# EMMC_SDcard.net
KiCad netlist of a schematic drawn in Altium Designer
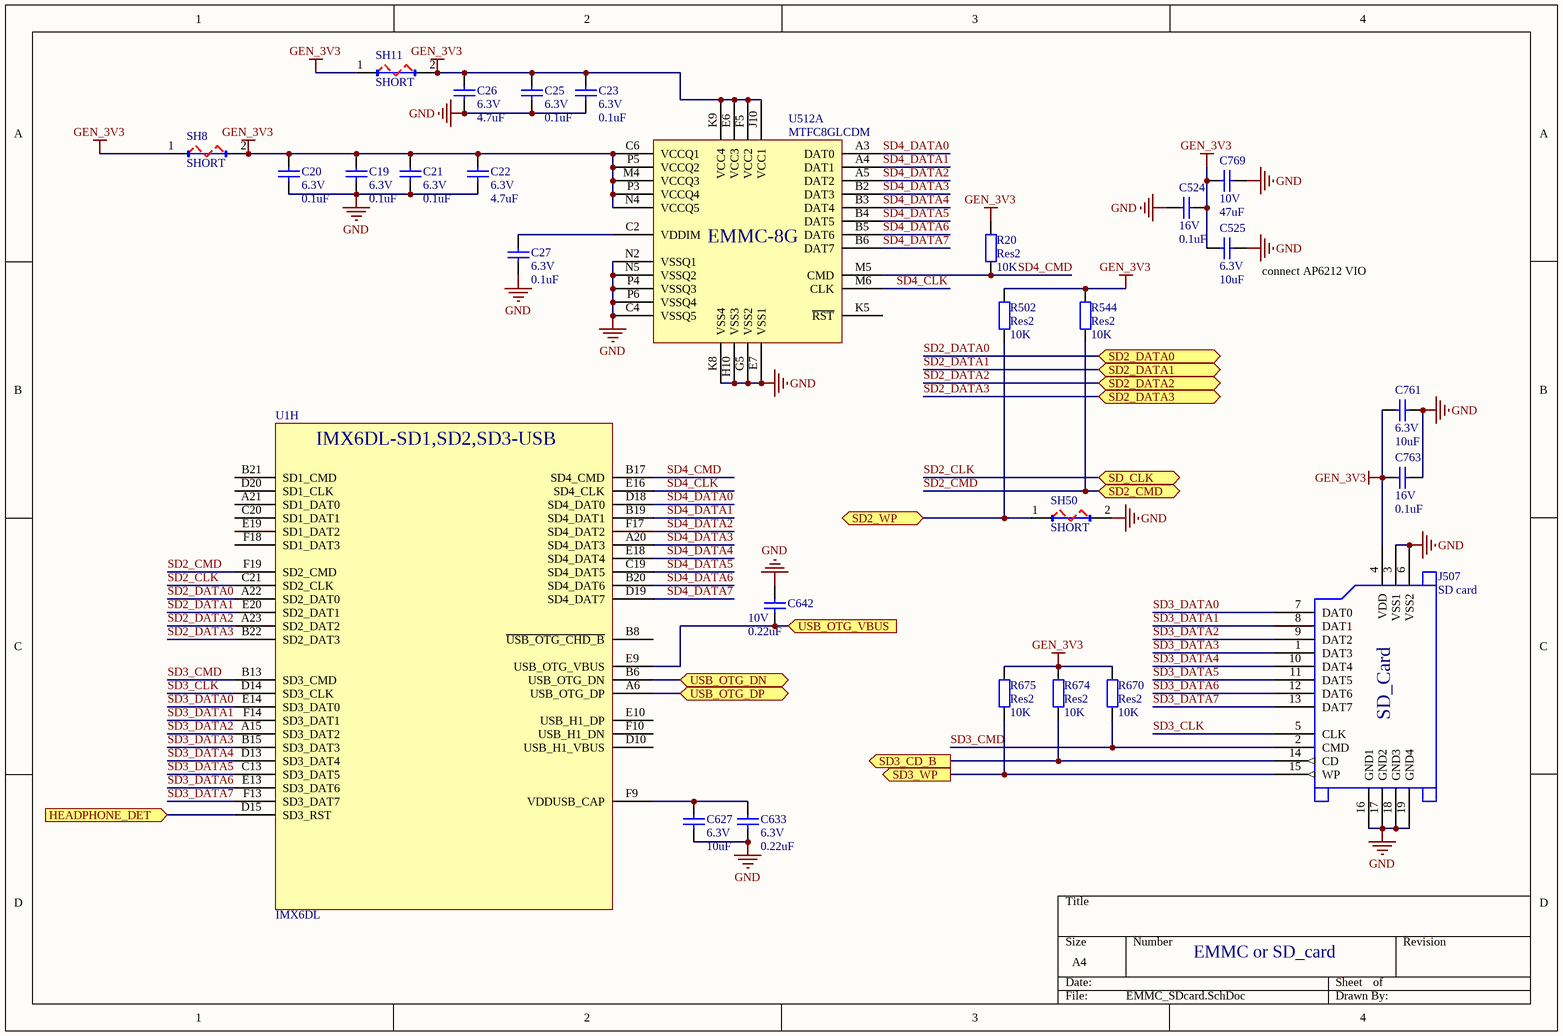
[diagram p0: EMMC_SDcard.SchDoc]

(export (version "E")
  (design (tool "Eeschema 10.0.6"))
  (components
    (comp (ref "C19")
      (value "6.3V")
      (footprint "0201")
      (description "Capacitor")
      (fields (field (name "ALTIUM_VALUE") "0.1uF") (field (name "PUBLISHER") "Altium Limited"))
      (libsource (lib "Miscellaneous Devices") (part "Cap"))
    )
    (comp (ref "C20")
      (value "6.3V")
      (footprint "0201")
      (description "Capacitor")
      (fields (field (name "ALTIUM_VALUE") "0.1uF") (field (name "PUBLISHER") "Altium Limited"))
      (libsource (lib "Miscellaneous Devices") (part "Cap"))
    )
    (comp (ref "C21")
      (value "6.3V")
      (footprint "0201")
      (description "Capacitor")
      (fields (field (name "ALTIUM_VALUE") "0.1uF") (field (name "PUBLISHER") "Altium Limited"))
      (libsource (lib "Miscellaneous Devices") (part "Cap"))
    )
    (comp (ref "C22")
      (value "6.3V")
      (footprint "0603")
      (description "Capacitor")
      (fields (field (name "ALTIUM_VALUE") "4.7uF") (field (name "PUBLISHER") "Altium Limited"))
      (libsource (lib "Miscellaneous Devices") (part "Cap"))
    )
    (comp (ref "C23")
      (value "6.3V")
      (footprint "0201")
      (description "Capacitor")
      (fields (field (name "ALTIUM_VALUE") "0.1uF") (field (name "PUBLISHER") "Altium Limited"))
      (libsource (lib "Miscellaneous Devices") (part "Cap"))
    )
    (comp (ref "C25")
      (value "6.3V")
      (footprint "0201")
      (description "Capacitor")
      (fields (field (name "ALTIUM_VALUE") "0.1uF") (field (name "PUBLISHER") "Altium Limited"))
      (libsource (lib "Miscellaneous Devices") (part "Cap"))
    )
    (comp (ref "C26")
      (value "6.3V")
      (footprint "0603")
      (description "Capacitor")
      (fields (field (name "ALTIUM_VALUE") "4.7uF") (field (name "PUBLISHER") "Altium Limited"))
      (libsource (lib "Miscellaneous Devices") (part "Cap"))
    )
    (comp (ref "C27")
      (value "6.3V")
      (footprint "0201")
      (description "Capacitor")
      (fields (field (name "ALTIUM_VALUE") "0.1uF") (field (name "PUBLISHER") "Altium Limited"))
      (libsource (lib "Miscellaneous Devices") (part "Cap"))
    )
    (comp (ref "C524")
      (value "16V")
      (footprint "0402")
      (description "Capacitor")
      (fields (field (name "ALTIUM_VALUE") "0.1uF") (field (name "PUBLISHER") "Altium Limited"))
      (libsource (lib "Miscellaneous Devices") (part "Cap"))
    )
    (comp (ref "C525")
      (value "6.3V")
      (footprint "0603")
      (description "Capacitor")
      (fields (field (name "ALTIUM_VALUE") "10uF") (field (name "PUBLISHER") "Altium Limited"))
      (libsource (lib "Miscellaneous Devices") (part "Cap"))
    )
    (comp (ref "C627")
      (value "6.3V")
      (footprint "0603")
      (description "Capacitor")
      (fields (field (name "ALTIUM_VALUE") "10uF") (field (name "PUBLISHER") "Altium Limited"))
      (libsource (lib "Miscellaneous Devices") (part "Cap"))
    )
    (comp (ref "C633")
      (value "6.3V")
      (footprint "0201")
      (description "Capacitor")
      (fields (field (name "ALTIUM_VALUE") "0.22uF") (field (name "PUBLISHER") "Altium Limited"))
      (libsource (lib "Miscellaneous Devices") (part "Cap"))
    )
    (comp (ref "C642")
      (value "10V")
      (footprint "0201")
      (description "Capacitor")
      (fields (field (name "ALTIUM_VALUE") "0.22uF") (field (name "PUBLISHER") "Altium Limited"))
      (libsource (lib "Miscellaneous Devices") (part "Cap"))
    )
    (comp (ref "C761")
      (value "6.3V")
      (footprint "0603")
      (description "Capacitor")
      (fields (field (name "ALTIUM_VALUE") "10uF") (field (name "PUBLISHER") "Altium Limited"))
      (libsource (lib "Miscellaneous Devices") (part "Cap"))
    )
    (comp (ref "C763")
      (value "16V")
      (footprint "0402")
      (description "Capacitor")
      (fields (field (name "ALTIUM_VALUE") "0.1uF") (field (name "PUBLISHER") "Altium Limited"))
      (libsource (lib "Miscellaneous Devices") (part "Cap"))
    )
    (comp (ref "C769")
      (value "10V")
      (footprint "nonpolarity_cap_1206")
      (description "Capacitor")
      (fields (field (name "ALTIUM_VALUE") "47uF") (field (name "PUBLISHER") "Altium Limited"))
      (libsource (lib "Miscellaneous Devices") (part "Cap"))
    )
    (comp (ref "J507") (value "SD card") (footprint "SD_card") (libsource (lib "IMX6DL") (part "SD card")))
    (comp (ref "R20")
      (value "Res2")
      (footprint "0402")
      (description "Resistor")
      (fields (field (name "ALTIUM_VALUE") "10K") (field (name "PUBLISHER") "Altium Limited"))
      (libsource (lib "Miscellaneous Devices") (part "Res2"))
    )
    (comp (ref "R502")
      (value "Res2")
      (footprint "0402")
      (description "Resistor")
      (fields (field (name "ALTIUM_VALUE") "10K") (field (name "PUBLISHER") "Altium Limited"))
      (libsource (lib "Miscellaneous Devices") (part "Res2"))
    )
    (comp (ref "R544")
      (value "Res2")
      (footprint "0402")
      (description "Resistor")
      (fields (field (name "ALTIUM_VALUE") "10K") (field (name "PUBLISHER") "Altium Limited"))
      (libsource (lib "Miscellaneous Devices") (part "Res2"))
    )
    (comp (ref "R670")
      (value "Res2")
      (footprint "0402")
      (description "Resistor")
      (fields (field (name "ALTIUM_VALUE") "10K") (field (name "PUBLISHER") "Altium Limited"))
      (libsource (lib "Miscellaneous Devices") (part "Res2"))
    )
    (comp (ref "R674")
      (value "Res2")
      (footprint "0402")
      (description "Resistor")
      (fields (field (name "ALTIUM_VALUE") "10K") (field (name "PUBLISHER") "Altium Limited"))
      (libsource (lib "Miscellaneous Devices") (part "Res2"))
    )
    (comp (ref "R675")
      (value "Res2")
      (footprint "0402")
      (description "Resistor")
      (fields (field (name "ALTIUM_VALUE") "10K") (field (name "PUBLISHER") "Altium Limited"))
      (libsource (lib "Miscellaneous Devices") (part "Res2"))
    )
    (comp (ref "SH8") (value "SHORT") (footprint "SHORT_SH") (libsource (lib "IMX6DL") (part "SOLDER SHORT")))
    (comp (ref "SH11")
      (value "SHORT")
      (footprint "SHORT_SH")
      (libsource (lib "IMX6DL") (part "SOLDER SHORT"))
    )
    (comp (ref "SH50")
      (value "SHORT")
      (footprint "SHORT_SH")
      (libsource (lib "IMX6DL") (part "SOLDER SHORT"))
    )
    (comp (ref "U1")
      (value "IMX6DL")
      (footprint "IMX6DL-BGA624x25")
      (libsource (lib "IMX6DL") (part "IMX6DL"))
    )
    (comp (ref "U512A")
      (value "MTFC8GLCDM")
      (footprint "SDIN8DE2-4G-EMMC-BGA153")
      (libsource (lib "IMX6DL") (part "MTFC8GLCDM-emmc"))
    )
  )
  (nets
    (net (code "1") (name "/HEADPHONE_DET") (class "Default")
      (node (ref "U1") (pin "D15") (pinfunction "SD3_RST_D15") (pintype "passive"))
    )
    (net (code "2") (name "/SD2_CLK") (class "Default")
      (node (ref "U1") (pin "C21") (pinfunction "SD2_CLK_C21") (pintype "passive"))
    )
    (net (code "3") (name "/SD2_CMD") (class "Default")
      (node (ref "R544") (pin "1") (pinfunction "1_1") (pintype "passive"))
      (node (ref "U1") (pin "F19") (pinfunction "SD2_CMD_F19") (pintype "passive"))
    )
    (net (code "4") (name "/SD2_DATA0") (class "Default")
      (node (ref "U1") (pin "A22") (pinfunction "SD2_DAT0_A22") (pintype "passive"))
    )
    (net (code "5") (name "/SD2_DATA1") (class "Default")
      (node (ref "U1") (pin "E20") (pinfunction "SD2_DAT1_E20") (pintype "passive"))
    )
    (net (code "6") (name "/SD2_DATA2") (class "Default")
      (node (ref "U1") (pin "A23") (pinfunction "SD2_DAT2_A23") (pintype "passive"))
    )
    (net (code "7") (name "/SD2_DATA3") (class "Default")
      (node (ref "U1") (pin "B22") (pinfunction "SD2_DAT3_B22") (pintype "passive"))
    )
    (net (code "8") (name "/SD2_WP") (class "Default")
      (node (ref "R502") (pin "1") (pinfunction "1_1") (pintype "passive"))
      (node (ref "SH50") (pin "1") (pinfunction "VCCIO_1") (pintype "passive"))
    )
    (net (code "9") (name "/SD3_CD_B") (class "Default")
      (node (ref "J507") (pin "14") (pinfunction "CD_14") (pintype "output"))
      (node (ref "R674") (pin "1") (pinfunction "1_1") (pintype "passive"))
    )
    (net (code "10") (name "/SD3_CLK") (class "Default")
      (node (ref "J507") (pin "5") (pinfunction "CLK_5") (pintype "passive"))
      (node (ref "U1") (pin "D14") (pinfunction "SD3_CLK_D14") (pintype "passive"))
    )
    (net (code "11") (name "/SD3_CMD") (class "Default")
      (node (ref "J507") (pin "2") (pinfunction "CMD_2") (pintype "passive"))
      (node (ref "R670") (pin "1") (pinfunction "1_1") (pintype "passive"))
      (node (ref "U1") (pin "B13") (pinfunction "SD3_CMD_B13") (pintype "passive"))
    )
    (net (code "12") (name "/SD3_DATA0") (class "Default")
      (node (ref "J507") (pin "7") (pinfunction "DAT0_7") (pintype "passive"))
      (node (ref "U1") (pin "E14") (pinfunction "SD3_DAT0_E14") (pintype "passive"))
    )
    (net (code "13") (name "/SD3_DATA1") (class "Default")
      (node (ref "J507") (pin "8") (pinfunction "DAT1_8") (pintype "passive"))
      (node (ref "U1") (pin "F14") (pinfunction "SD3_DAT1_F14") (pintype "passive"))
    )
    (net (code "14") (name "/SD3_DATA2") (class "Default")
      (node (ref "J507") (pin "9") (pinfunction "DAT2_9") (pintype "passive"))
      (node (ref "U1") (pin "A15") (pinfunction "SD3_DAT2_A15") (pintype "passive"))
    )
    (net (code "15") (name "/SD3_DATA3") (class "Default")
      (node (ref "J507") (pin "1") (pinfunction "DAT3_1") (pintype "passive"))
      (node (ref "U1") (pin "B15") (pinfunction "SD3_DAT3_B15") (pintype "passive"))
    )
    (net (code "16") (name "/SD3_DATA4") (class "Default")
      (node (ref "J507") (pin "10") (pinfunction "DAT4_10") (pintype "passive"))
      (node (ref "U1") (pin "D13") (pinfunction "SD3_DAT4_D13") (pintype "passive"))
    )
    (net (code "17") (name "/SD3_DATA5") (class "Default")
      (node (ref "J507") (pin "11") (pinfunction "DAT5_11") (pintype "passive"))
      (node (ref "U1") (pin "C13") (pinfunction "SD3_DAT5_C13") (pintype "passive"))
    )
    (net (code "18") (name "/SD3_DATA6") (class "Default")
      (node (ref "J507") (pin "12") (pinfunction "DAT6_12") (pintype "passive"))
      (node (ref "U1") (pin "E13") (pinfunction "SD3_DAT6_E13") (pintype "passive"))
    )
    (net (code "19") (name "/SD3_DATA7") (class "Default")
      (node (ref "J507") (pin "13") (pinfunction "DAT7_13") (pintype "passive"))
      (node (ref "U1") (pin "F13") (pinfunction "SD3_DAT7_F13") (pintype "passive"))
    )
    (net (code "20") (name "/SD3_WP") (class "Default")
      (node (ref "J507") (pin "15") (pinfunction "WP_15") (pintype "output"))
      (node (ref "R675") (pin "1") (pinfunction "1_1") (pintype "passive"))
    )
    (net (code "21") (name "/SD4_CLK") (class "Default")
      (node (ref "U1") (pin "E16") (pinfunction "SD4_CLK_E16") (pintype "passive"))
      (node (ref "U512A") (pin "M6") (pinfunction "CLK_M6") (pintype "passive"))
    )
    (net (code "22") (name "/SD4_CMD") (class "Default")
      (node (ref "R20") (pin "1") (pinfunction "1_1") (pintype "passive"))
      (node (ref "U1") (pin "B17") (pinfunction "SD4_CMD_B17") (pintype "passive"))
      (node (ref "U512A") (pin "M5") (pinfunction "CMD_M5") (pintype "passive"))
    )
    (net (code "23") (name "/SD4_DATA0") (class "Default")
      (node (ref "U1") (pin "D18") (pinfunction "SD4_DAT0_D18") (pintype "passive"))
      (node (ref "U512A") (pin "A3") (pinfunction "DAT0_A3") (pintype "passive"))
    )
    (net (code "24") (name "/SD4_DATA1") (class "Default")
      (node (ref "U1") (pin "B19") (pinfunction "SD4_DAT1_B19") (pintype "passive"))
      (node (ref "U512A") (pin "A4") (pinfunction "DAT1_A4") (pintype "passive"))
    )
    (net (code "25") (name "/SD4_DATA2") (class "Default")
      (node (ref "U1") (pin "F17") (pinfunction "SD4_DAT2_F17") (pintype "passive"))
      (node (ref "U512A") (pin "A5") (pinfunction "DAT2_A5") (pintype "passive"))
    )
    (net (code "26") (name "/SD4_DATA3") (class "Default")
      (node (ref "U1") (pin "A20") (pinfunction "SD4_DAT3_A20") (pintype "passive"))
      (node (ref "U512A") (pin "B2") (pinfunction "DAT3_B2") (pintype "passive"))
    )
    (net (code "27") (name "/SD4_DATA4") (class "Default")
      (node (ref "U1") (pin "E18") (pinfunction "SD4_DAT4_E18") (pintype "passive"))
      (node (ref "U512A") (pin "B3") (pinfunction "DAT4_B3") (pintype "passive"))
    )
    (net (code "28") (name "/SD4_DATA5") (class "Default")
      (node (ref "U1") (pin "C19") (pinfunction "SD4_DAT5_C19") (pintype "passive"))
      (node (ref "U512A") (pin "B4") (pinfunction "DAT5_B4") (pintype "passive"))
    )
    (net (code "29") (name "/SD4_DATA6") (class "Default")
      (node (ref "U1") (pin "B20") (pinfunction "SD4_DAT6_B20") (pintype "passive"))
      (node (ref "U512A") (pin "B5") (pinfunction "DAT6_B5") (pintype "passive"))
    )
    (net (code "30") (name "/SD4_DATA7") (class "Default")
      (node (ref "U1") (pin "D19") (pinfunction "SD4_DAT7_D19") (pintype "passive"))
      (node (ref "U512A") (pin "B6") (pinfunction "DAT7_B6") (pintype "passive"))
    )
    (net (code "31") (name "/USB_OTG_DN") (class "Default")
      (node (ref "U1") (pin "B6") (pinfunction "USB_OTG_DN_B6") (pintype "passive"))
    )
    (net (code "32") (name "/USB_OTG_DP") (class "Default")
      (node (ref "U1") (pin "A6") (pinfunction "USB_OTG_DP_A6") (pintype "passive"))
    )
    (net (code "33") (name "/USB_OTG_VBUS") (class "Default")
      (node (ref "C642") (pin "1") (pinfunction "1_1") (pintype "passive"))
      (node (ref "U1") (pin "E9") (pinfunction "USB_OTG_VBUS_E9") (pintype "passive"))
    )
    (net (code "34") (name "GEN_3V3") (class "Default")
      (node (ref "C19") (pin "2") (pinfunction "2_2") (pintype "passive"))
      (node (ref "C20") (pin "2") (pinfunction "2_2") (pintype "passive"))
      (node (ref "C21") (pin "2") (pinfunction "2_2") (pintype "passive"))
      (node (ref "C22") (pin "2") (pinfunction "2_2") (pintype "passive"))
      (node (ref "C23") (pin "2") (pinfunction "2_2") (pintype "passive"))
      (node (ref "C25") (pin "2") (pinfunction "2_2") (pintype "passive"))
      (node (ref "C26") (pin "2") (pinfunction "2_2") (pintype "passive"))
      (node (ref "C524") (pin "1") (pinfunction "1_1") (pintype "passive"))
      (node (ref "C525") (pin "1") (pinfunction "1_1") (pintype "passive"))
      (node (ref "C761") (pin "1") (pinfunction "1_1") (pintype "passive"))
      (node (ref "C763") (pin "1") (pinfunction "1_1") (pintype "passive"))
      (node (ref "C769") (pin "1") (pinfunction "1_1") (pintype "passive"))
      (node (ref "J507") (pin "4") (pinfunction "VDD_4") (pintype "passive"))
      (node (ref "R20") (pin "2") (pinfunction "2_2") (pintype "passive"))
      (node (ref "R502") (pin "2") (pinfunction "2_2") (pintype "passive"))
      (node (ref "R544") (pin "2") (pinfunction "2_2") (pintype "passive"))
      (node (ref "R670") (pin "2") (pinfunction "2_2") (pintype "passive"))
      (node (ref "R674") (pin "2") (pinfunction "2_2") (pintype "passive"))
      (node (ref "R675") (pin "2") (pinfunction "2_2") (pintype "passive"))
      (node (ref "SH11") (pin "1") (pinfunction "VCCIO_1") (pintype "passive"))
      (node (ref "SH11") (pin "2") (pinfunction "VCCIO_2") (pintype "passive"))
      (node (ref "SH8") (pin "1") (pinfunction "VCCIO_1") (pintype "passive"))
      (node (ref "SH8") (pin "2") (pinfunction "VCCIO_2") (pintype "passive"))
      (node (ref "U512A") (pin "C6") (pinfunction "VCCQ1_C6") (pintype "passive"))
      (node (ref "U512A") (pin "E6") (pinfunction "VCC3_E6") (pintype "passive"))
      (node (ref "U512A") (pin "F5") (pinfunction "VCC2_F5") (pintype "passive"))
      (node (ref "U512A") (pin "J10") (pinfunction "VCC1_J10") (pintype "passive"))
      (node (ref "U512A") (pin "K9") (pinfunction "VCC4_K9") (pintype "passive"))
      (node (ref "U512A") (pin "M4") (pinfunction "VCCQ3_M4") (pintype "passive"))
      (node (ref "U512A") (pin "N4") (pinfunction "VCCQ5_N4") (pintype "passive"))
      (node (ref "U512A") (pin "P3") (pinfunction "VCCQ4_P3") (pintype "passive"))
      (node (ref "U512A") (pin "P5") (pinfunction "VCCQ2_P5") (pintype "passive"))
    )
    (net (code "35") (name "GND") (class "Default")
      (node (ref "C19") (pin "1") (pinfunction "1_1") (pintype "passive"))
      (node (ref "C20") (pin "1") (pinfunction "1_1") (pintype "passive"))
      (node (ref "C21") (pin "1") (pinfunction "1_1") (pintype "passive"))
      (node (ref "C22") (pin "1") (pinfunction "1_1") (pintype "passive"))
      (node (ref "C23") (pin "1") (pinfunction "1_1") (pintype "passive"))
      (node (ref "C25") (pin "1") (pinfunction "1_1") (pintype "passive"))
      (node (ref "C26") (pin "1") (pinfunction "1_1") (pintype "passive"))
      (node (ref "C27") (pin "1") (pinfunction "1_1") (pintype "passive"))
      (node (ref "C524") (pin "2") (pinfunction "2_2") (pintype "passive"))
      (node (ref "C525") (pin "2") (pinfunction "2_2") (pintype "passive"))
      (node (ref "C627") (pin "1") (pinfunction "1_1") (pintype "passive"))
      (node (ref "C633") (pin "1") (pinfunction "1_1") (pintype "passive"))
      (node (ref "C642") (pin "2") (pinfunction "2_2") (pintype "passive"))
      (node (ref "C761") (pin "2") (pinfunction "2_2") (pintype "passive"))
      (node (ref "C763") (pin "2") (pinfunction "2_2") (pintype "passive"))
      (node (ref "C769") (pin "2") (pinfunction "2_2") (pintype "passive"))
      (node (ref "J507") (pin "16") (pinfunction "GND1_16") (pintype "passive"))
      (node (ref "J507") (pin "17") (pinfunction "GND2_17") (pintype "passive"))
      (node (ref "J507") (pin "18") (pinfunction "GND3_18") (pintype "passive"))
      (node (ref "J507") (pin "19") (pinfunction "GND4_19") (pintype "passive"))
      (node (ref "J507") (pin "3") (pinfunction "VSS1_3") (pintype "passive"))
      (node (ref "J507") (pin "6") (pinfunction "VSS2_6") (pintype "passive"))
      (node (ref "SH50") (pin "2") (pinfunction "VCCIO_2") (pintype "passive"))
      (node (ref "U512A") (pin "C4") (pinfunction "VSSQ5_C4") (pintype "passive"))
      (node (ref "U512A") (pin "E7") (pinfunction "VSS1_E7") (pintype "passive"))
      (node (ref "U512A") (pin "G5") (pinfunction "VSS2_G5") (pintype "passive"))
      (node (ref "U512A") (pin "H10") (pinfunction "VSS3_H10") (pintype "passive"))
      (node (ref "U512A") (pin "K8") (pinfunction "VSS4_K8") (pintype "passive"))
      (node (ref "U512A") (pin "N2") (pinfunction "VSSQ1_N2") (pintype "passive"))
      (node (ref "U512A") (pin "N5") (pinfunction "VSSQ2_N5") (pintype "passive"))
      (node (ref "U512A") (pin "P4") (pinfunction "VSSQ3_P4") (pintype "passive"))
      (node (ref "U512A") (pin "P6") (pinfunction "VSSQ4_P6") (pintype "passive"))
    )
    (net (code "36") (name "Net-(U1H-VDDUSB_CAP)") (class "Default")
      (node (ref "C627") (pin "2") (pinfunction "2_2") (pintype "passive"))
      (node (ref "C633") (pin "2") (pinfunction "2_2") (pintype "passive"))
      (node (ref "U1") (pin "F9") (pinfunction "VDDUSB_CAP_F9") (pintype "passive"))
    )
    (net (code "37") (name "Net-(U512A-VDDIM)") (class "Default")
      (node (ref "C27") (pin "2") (pinfunction "2_2") (pintype "passive"))
      (node (ref "U512A") (pin "C2") (pinfunction "VDDIM_C2") (pintype "passive"))
    )
    (net (code "38") (name "unconnected-(U1H-SD1_CLK-PadD20)") (class "Default")
      (node (ref "U1") (pin "D20") (pinfunction "SD1_CLK_D20") (pintype "passive"))
    )
    (net (code "39") (name "unconnected-(U1H-SD1_CMD-PadB21)") (class "Default")
      (node (ref "U1") (pin "B21") (pinfunction "SD1_CMD_B21") (pintype "passive"))
    )
    (net (code "40") (name "unconnected-(U1H-SD1_DAT0-PadA21)") (class "Default")
      (node (ref "U1") (pin "A21") (pinfunction "SD1_DAT0_A21") (pintype "passive"))
    )
    (net (code "41") (name "unconnected-(U1H-SD1_DAT1-PadC20)") (class "Default")
      (node (ref "U1") (pin "C20") (pinfunction "SD1_DAT1_C20") (pintype "passive"))
    )
    (net (code "42") (name "unconnected-(U1H-SD1_DAT2-PadE19)") (class "Default")
      (node (ref "U1") (pin "E19") (pinfunction "SD1_DAT2_E19") (pintype "passive"))
    )
    (net (code "43") (name "unconnected-(U1H-SD1_DAT3-PadF18)") (class "Default")
      (node (ref "U1") (pin "F18") (pinfunction "SD1_DAT3_F18") (pintype "passive"))
    )
    (net (code "44") (name "unconnected-(U1H-USB_H1_DN-PadF10)") (class "Default")
      (node (ref "U1") (pin "F10") (pinfunction "USB_H1_DN_F10") (pintype "passive"))
    )
    (net (code "45") (name "unconnected-(U1H-USB_H1_DP-PadE10)") (class "Default")
      (node (ref "U1") (pin "E10") (pinfunction "USB_H1_DP_E10") (pintype "passive"))
    )
    (net (code "46") (name "unconnected-(U1H-USB_H1_VBUS-PadD10)") (class "Default")
      (node (ref "U1") (pin "D10") (pinfunction "USB_H1_VBUS_D10") (pintype "passive"))
    )
    (net (code "47") (name "unconnected-(U1H-~{USB_OTG_CHD_B}-PadB8)") (class "Default")
      (node (ref "U1") (pin "B8") (pinfunction "~{USB_OTG_CHD_B}_B8") (pintype "passive"))
    )
    (net (code "48") (name "unconnected-(U512A-~{RST}-PadK5)") (class "Default")
      (node (ref "U512A") (pin "K5") (pinfunction "~{RST}_K5") (pintype "passive"))
    )
  )
)
